# axiom_beta_interface_dummy_v0_11_1c4a0d4.net
KiCad netlist of a schematic drawn in EAGLE
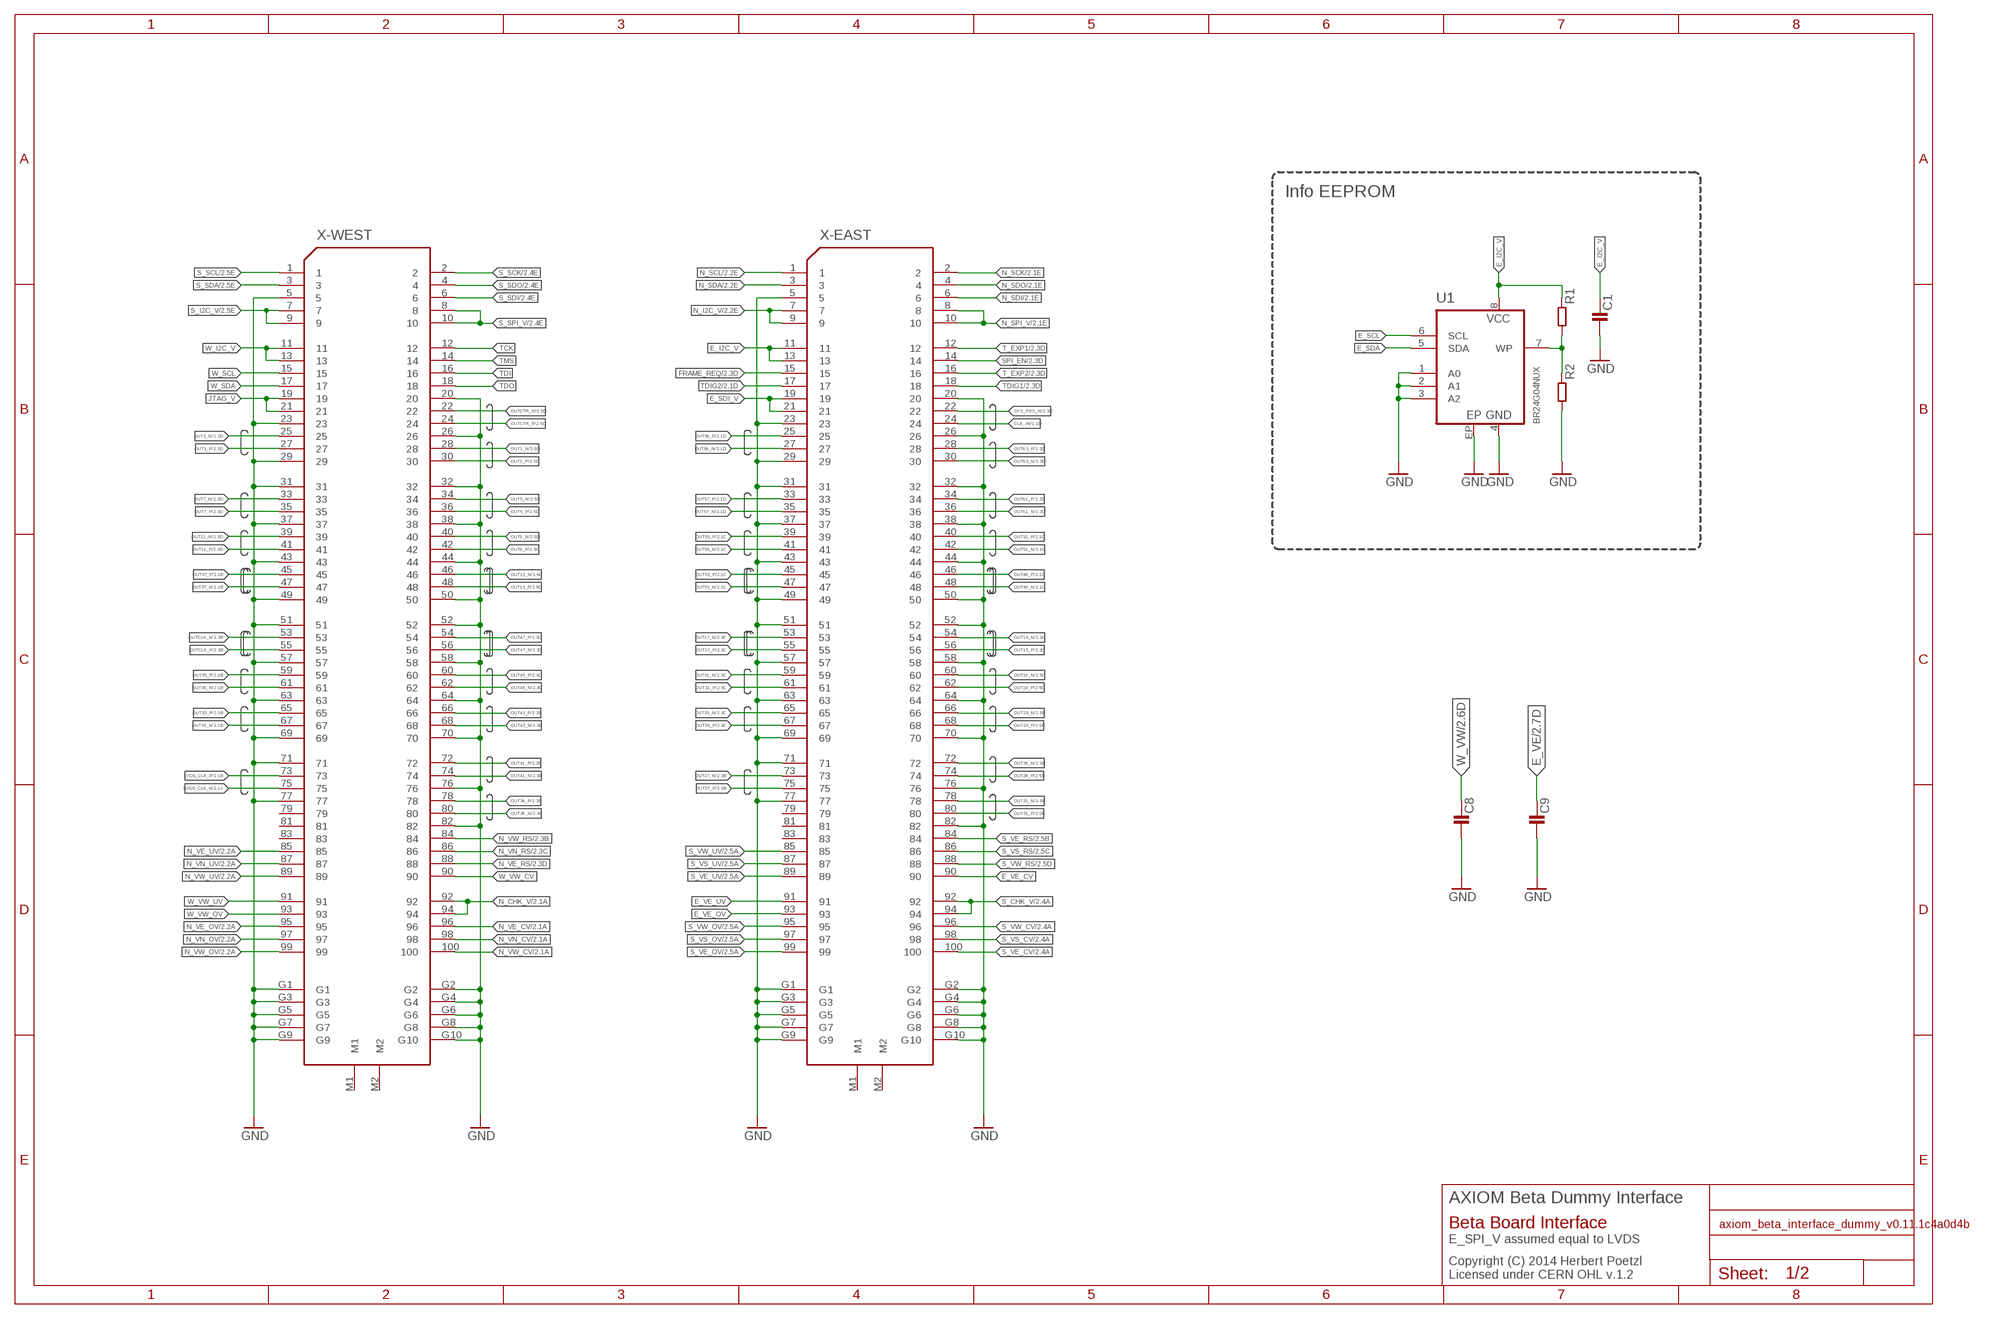
[diagram p0: schematic, sheet 1]
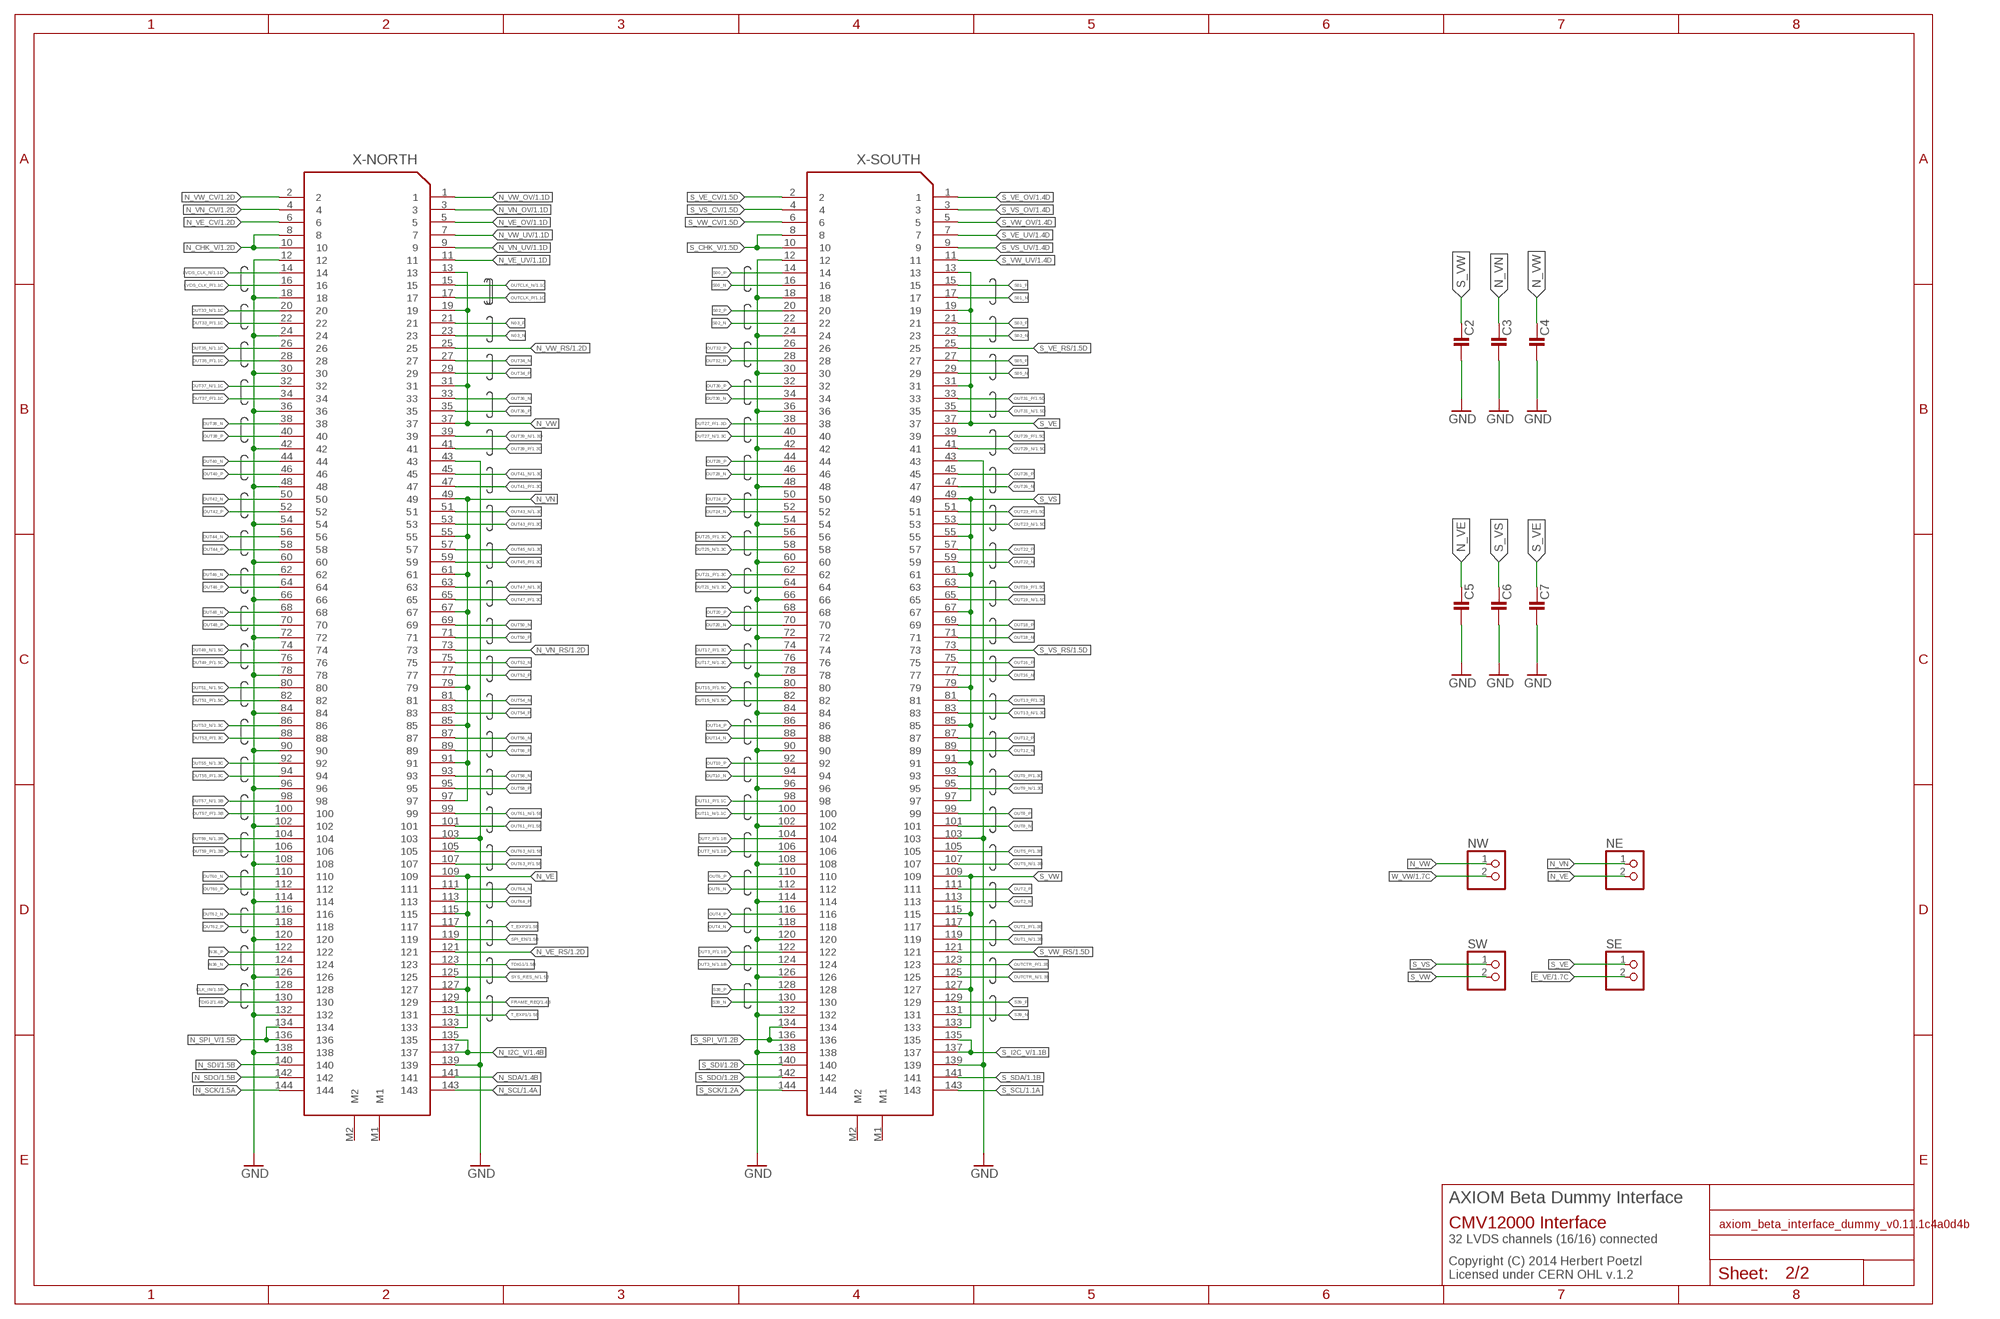
[diagram p1: schematic, sheet 2]

(export (version "E")
  (design (tool "Eeschema 10.0.6"))
  (components
    (comp (ref "C2")
      (value "C0805-B")
      (footprint "eagle-import:0805-B")
      (libsource (lib "eagle-import") (part "C0805-B"))
    )
    (comp (ref "C3")
      (value "C0805-B")
      (footprint "eagle-import:0805-B")
      (libsource (lib "eagle-import") (part "C0805-B"))
    )
    (comp (ref "C4")
      (value "C0805-B")
      (footprint "eagle-import:0805-B")
      (libsource (lib "eagle-import") (part "C0805-B"))
    )
    (comp (ref "C5")
      (value "C0805-B")
      (footprint "eagle-import:0805-B")
      (libsource (lib "eagle-import") (part "C0805-B"))
    )
    (comp (ref "C6")
      (value "C0805-B")
      (footprint "eagle-import:0805-B")
      (libsource (lib "eagle-import") (part "C0805-B"))
    )
    (comp (ref "C7")
      (value "C0805-B")
      (footprint "eagle-import:0805-B")
      (libsource (lib "eagle-import") (part "C0805-B"))
    )
    (comp (ref "NE")
      (value "PINHD-1X02_2.54")
      (footprint "eagle-import:1X02")
      (libsource (lib "eagle-import") (part "PINHD-1X02_2.54"))
    )
    (comp (ref "NW")
      (value "PINHD-1X02_2.54")
      (footprint "eagle-import:1X02")
      (libsource (lib "eagle-import") (part "PINHD-1X02_2.54"))
    )
    (comp (ref "SE")
      (value "PINHD-1X02_2.54")
      (footprint "eagle-import:1X02")
      (libsource (lib "eagle-import") (part "PINHD-1X02_2.54"))
    )
    (comp (ref "SW")
      (value "PINHD-1X02_2.54")
      (footprint "eagle-import:1X02")
      (libsource (lib "eagle-import") (part "PINHD-1X02_2.54"))
    )
    (comp (ref "X-NORTH")
      (value "FX10-144S")
      (footprint "eagle-import:FX10A-144S")
      (libsource (lib "eagle-import") (part "FX10-144S"))
    )
    (comp (ref "X-SOUTH")
      (value "FX10-144S")
      (footprint "eagle-import:FX10A-144S")
      (libsource (lib "eagle-import") (part "FX10-144S"))
    )
    (comp (ref "C1")
      (value "C0402-B")
      (footprint "eagle-import:0402-B")
      (libsource (lib "eagle-import") (part "C0402-B"))
    )
    (comp (ref "C8")
      (value "C0805-B")
      (footprint "eagle-import:0805-B")
      (libsource (lib "eagle-import") (part "C0805-B"))
    )
    (comp (ref "C9")
      (value "C0805-B")
      (footprint "eagle-import:0805-B")
      (libsource (lib "eagle-import") (part "C0805-B"))
    )
    (comp (ref "R1")
      (value "R0402-B")
      (footprint "eagle-import:0402-B")
      (libsource (lib "eagle-import") (part "R0402-B"))
    )
    (comp (ref "R2")
      (value "R0402-B")
      (footprint "eagle-import:0402-B")
      (libsource (lib "eagle-import") (part "R0402-B"))
    )
    (comp (ref "U1")
      (value "BR24G04NUX")
      (footprint "eagle-import:DFN200X300X100-9N")
      (libsource (lib "eagle-import") (part "BR24G04NUX"))
    )
    (comp (ref "X-EAST")
      (value "FX10-100/10P")
      (footprint "eagle-import:FX10A-100P_10")
      (libsource (lib "eagle-import") (part "FX10-100/10P"))
    )
    (comp (ref "X-WEST")
      (value "FX10-100/10P")
      (footprint "eagle-import:FX10A-100P_10")
      (libsource (lib "eagle-import") (part "FX10-100/10P"))
    )
  )
  (nets
    (net (code "1") (name "CLK_IN") (class "Default")
      (node (ref "X-EAST") (pin "24") (pinfunction "24_24") (pintype "bidirectional"))
      (node (ref "X-NORTH") (pin "128") (pinfunction "128_128") (pintype "bidirectional"))
    )
    (net (code "2") (name "E_I2C_V") (class "Default")
      (node (ref "C1") (pin "1") (pinfunction "1_1") (pintype "passive"))
      (node (ref "R1") (pin "1") (pinfunction "1_1") (pintype "passive"))
      (node (ref "U1") (pin "8") (pinfunction "VCC_8") (pintype "power_in"))
      (node (ref "X-EAST") (pin "11") (pinfunction "11_11") (pintype "bidirectional"))
      (node (ref "X-EAST") (pin "13") (pinfunction "13_13") (pintype "bidirectional"))
    )
    (net (code "3") (name "E_SCL") (class "Default")
      (node (ref "U1") (pin "6") (pinfunction "SCL_6") (pintype "input"))
    )
    (net (code "4") (name "E_SDA") (class "Default")
      (node (ref "U1") (pin "5") (pinfunction "SDA_5") (pintype "bidirectional"))
    )
    (net (code "5") (name "E_SDI_V") (class "Default")
      (node (ref "X-EAST") (pin "19") (pinfunction "19_19") (pintype "bidirectional"))
      (node (ref "X-EAST") (pin "21") (pinfunction "21_21") (pintype "bidirectional"))
    )
    (net (code "6") (name "E_VE") (class "Default")
      (node (ref "C9") (pin "1") (pinfunction "1_1") (pintype "passive"))
      (node (ref "SE") (pin "2") (pinfunction "2_2") (pintype "passive"))
    )
    (net (code "7") (name "E_VE_CV") (class "Default")
      (node (ref "X-EAST") (pin "90") (pinfunction "90_90") (pintype "bidirectional"))
    )
    (net (code "8") (name "E_VE_OV") (class "Default")
      (node (ref "X-EAST") (pin "93") (pinfunction "93_93") (pintype "bidirectional"))
    )
    (net (code "9") (name "E_VE_UV") (class "Default")
      (node (ref "X-EAST") (pin "91") (pinfunction "91_91") (pintype "bidirectional"))
    )
    (net (code "10") (name "FRAME_REQ") (class "Default")
      (node (ref "X-EAST") (pin "15") (pinfunction "15_15") (pintype "bidirectional"))
      (node (ref "X-NORTH") (pin "129") (pinfunction "129_129") (pintype "bidirectional"))
    )
    (net (code "11") (name "GND") (class "Default")
      (node (ref "C1") (pin "2") (pinfunction "2_2") (pintype "passive"))
      (node (ref "C2") (pin "2") (pinfunction "2_2") (pintype "passive"))
      (node (ref "C3") (pin "2") (pinfunction "2_2") (pintype "passive"))
      (node (ref "C4") (pin "2") (pinfunction "2_2") (pintype "passive"))
      (node (ref "C5") (pin "2") (pinfunction "2_2") (pintype "passive"))
      (node (ref "C6") (pin "2") (pinfunction "2_2") (pintype "passive"))
      (node (ref "C7") (pin "2") (pinfunction "2_2") (pintype "passive"))
      (node (ref "C8") (pin "2") (pinfunction "2_2") (pintype "passive"))
      (node (ref "C9") (pin "2") (pinfunction "2_2") (pintype "passive"))
      (node (ref "R2") (pin "2") (pinfunction "2_2") (pintype "passive"))
      (node (ref "U1") (pin "1") (pinfunction "A0_1") (pintype "input"))
      (node (ref "U1") (pin "2") (pinfunction "A1_2") (pintype "input"))
      (node (ref "U1") (pin "3") (pinfunction "A2_3") (pintype "input"))
      (node (ref "U1") (pin "4") (pinfunction "GND_4") (pintype "passive"))
      (node (ref "U1") (pin "EP") (pinfunction "EP_EP") (pintype "passive"))
      (node (ref "X-EAST") (pin "20") (pinfunction "20_20") (pintype "bidirectional"))
      (node (ref "X-EAST") (pin "23") (pinfunction "23_23") (pintype "bidirectional"))
      (node (ref "X-EAST") (pin "26") (pinfunction "26_26") (pintype "bidirectional"))
      (node (ref "X-EAST") (pin "29") (pinfunction "29_29") (pintype "bidirectional"))
      (node (ref "X-EAST") (pin "31") (pinfunction "31_31") (pintype "bidirectional"))
      (node (ref "X-EAST") (pin "32") (pinfunction "32_32") (pintype "bidirectional"))
      (node (ref "X-EAST") (pin "37") (pinfunction "37_37") (pintype "bidirectional"))
      (node (ref "X-EAST") (pin "38") (pinfunction "38_38") (pintype "bidirectional"))
      (node (ref "X-EAST") (pin "43") (pinfunction "43_43") (pintype "bidirectional"))
      (node (ref "X-EAST") (pin "44") (pinfunction "44_44") (pintype "bidirectional"))
      (node (ref "X-EAST") (pin "49") (pinfunction "49_49") (pintype "bidirectional"))
      (node (ref "X-EAST") (pin "5") (pinfunction "5_5") (pintype "bidirectional"))
      (node (ref "X-EAST") (pin "50") (pinfunction "50_50") (pintype "bidirectional"))
      (node (ref "X-EAST") (pin "51") (pinfunction "51_51") (pintype "bidirectional"))
      (node (ref "X-EAST") (pin "52") (pinfunction "52_52") (pintype "bidirectional"))
      (node (ref "X-EAST") (pin "57") (pinfunction "57_57") (pintype "bidirectional"))
      (node (ref "X-EAST") (pin "58") (pinfunction "58_58") (pintype "bidirectional"))
      (node (ref "X-EAST") (pin "63") (pinfunction "63_63") (pintype "bidirectional"))
      (node (ref "X-EAST") (pin "64") (pinfunction "64_64") (pintype "bidirectional"))
      (node (ref "X-EAST") (pin "69") (pinfunction "69_69") (pintype "bidirectional"))
      (node (ref "X-EAST") (pin "70") (pinfunction "70_70") (pintype "bidirectional"))
      (node (ref "X-EAST") (pin "71") (pinfunction "71_71") (pintype "bidirectional"))
      (node (ref "X-EAST") (pin "76") (pinfunction "76_76") (pintype "bidirectional"))
      (node (ref "X-EAST") (pin "77") (pinfunction "77_77") (pintype "bidirectional"))
      (node (ref "X-EAST") (pin "82") (pinfunction "82_82") (pintype "bidirectional"))
      (node (ref "X-EAST") (pin "G1") (pinfunction "G1_G1") (pintype "bidirectional"))
      (node (ref "X-EAST") (pin "G10") (pinfunction "G10_G10") (pintype "bidirectional"))
      (node (ref "X-EAST") (pin "G2") (pinfunction "G2_G2") (pintype "bidirectional"))
      (node (ref "X-EAST") (pin "G3") (pinfunction "G3_G3") (pintype "bidirectional"))
      (node (ref "X-EAST") (pin "G4") (pinfunction "G4_G4") (pintype "bidirectional"))
      (node (ref "X-EAST") (pin "G5") (pinfunction "G5_G5") (pintype "bidirectional"))
      (node (ref "X-EAST") (pin "G6") (pinfunction "G6_G6") (pintype "bidirectional"))
      (node (ref "X-EAST") (pin "G7") (pinfunction "G7_G7") (pintype "bidirectional"))
      (node (ref "X-EAST") (pin "G8") (pinfunction "G8_G8") (pintype "bidirectional"))
      (node (ref "X-EAST") (pin "G9") (pinfunction "G9_G9") (pintype "bidirectional"))
      (node (ref "X-NORTH") (pin "102") (pinfunction "102_102") (pintype "bidirectional"))
      (node (ref "X-NORTH") (pin "103") (pinfunction "103_103") (pintype "bidirectional"))
      (node (ref "X-NORTH") (pin "108") (pinfunction "108_108") (pintype "bidirectional"))
      (node (ref "X-NORTH") (pin "114") (pinfunction "114_114") (pintype "bidirectional"))
      (node (ref "X-NORTH") (pin "12") (pinfunction "12_12") (pintype "bidirectional"))
      (node (ref "X-NORTH") (pin "120") (pinfunction "120_120") (pintype "bidirectional"))
      (node (ref "X-NORTH") (pin "126") (pinfunction "126_126") (pintype "bidirectional"))
      (node (ref "X-NORTH") (pin "132") (pinfunction "132_132") (pintype "bidirectional"))
      (node (ref "X-NORTH") (pin "138") (pinfunction "138_138") (pintype "bidirectional"))
      (node (ref "X-NORTH") (pin "139") (pinfunction "139_139") (pintype "bidirectional"))
      (node (ref "X-NORTH") (pin "18") (pinfunction "18_18") (pintype "bidirectional"))
      (node (ref "X-NORTH") (pin "24") (pinfunction "24_24") (pintype "bidirectional"))
      (node (ref "X-NORTH") (pin "30") (pinfunction "30_30") (pintype "bidirectional"))
      (node (ref "X-NORTH") (pin "36") (pinfunction "36_36") (pintype "bidirectional"))
      (node (ref "X-NORTH") (pin "42") (pinfunction "42_42") (pintype "bidirectional"))
      (node (ref "X-NORTH") (pin "43") (pinfunction "43_43") (pintype "bidirectional"))
      (node (ref "X-NORTH") (pin "48") (pinfunction "48_48") (pintype "bidirectional"))
      (node (ref "X-NORTH") (pin "54") (pinfunction "54_54") (pintype "bidirectional"))
      (node (ref "X-NORTH") (pin "60") (pinfunction "60_60") (pintype "bidirectional"))
      (node (ref "X-NORTH") (pin "66") (pinfunction "66_66") (pintype "bidirectional"))
      (node (ref "X-NORTH") (pin "72") (pinfunction "72_72") (pintype "bidirectional"))
      (node (ref "X-NORTH") (pin "78") (pinfunction "78_78") (pintype "bidirectional"))
      (node (ref "X-NORTH") (pin "84") (pinfunction "84_84") (pintype "bidirectional"))
      (node (ref "X-NORTH") (pin "90") (pinfunction "90_90") (pintype "bidirectional"))
      (node (ref "X-NORTH") (pin "96") (pinfunction "96_96") (pintype "bidirectional"))
      (node (ref "X-SOUTH") (pin "102") (pinfunction "102_102") (pintype "bidirectional"))
      (node (ref "X-SOUTH") (pin "103") (pinfunction "103_103") (pintype "bidirectional"))
      (node (ref "X-SOUTH") (pin "108") (pinfunction "108_108") (pintype "bidirectional"))
      (node (ref "X-SOUTH") (pin "114") (pinfunction "114_114") (pintype "bidirectional"))
      (node (ref "X-SOUTH") (pin "12") (pinfunction "12_12") (pintype "bidirectional"))
      (node (ref "X-SOUTH") (pin "120") (pinfunction "120_120") (pintype "bidirectional"))
      (node (ref "X-SOUTH") (pin "126") (pinfunction "126_126") (pintype "bidirectional"))
      (node (ref "X-SOUTH") (pin "132") (pinfunction "132_132") (pintype "bidirectional"))
      (node (ref "X-SOUTH") (pin "138") (pinfunction "138_138") (pintype "bidirectional"))
      (node (ref "X-SOUTH") (pin "139") (pinfunction "139_139") (pintype "bidirectional"))
      (node (ref "X-SOUTH") (pin "18") (pinfunction "18_18") (pintype "bidirectional"))
      (node (ref "X-SOUTH") (pin "24") (pinfunction "24_24") (pintype "bidirectional"))
      (node (ref "X-SOUTH") (pin "30") (pinfunction "30_30") (pintype "bidirectional"))
      (node (ref "X-SOUTH") (pin "36") (pinfunction "36_36") (pintype "bidirectional"))
      (node (ref "X-SOUTH") (pin "42") (pinfunction "42_42") (pintype "bidirectional"))
      (node (ref "X-SOUTH") (pin "43") (pinfunction "43_43") (pintype "bidirectional"))
      (node (ref "X-SOUTH") (pin "48") (pinfunction "48_48") (pintype "bidirectional"))
      (node (ref "X-SOUTH") (pin "54") (pinfunction "54_54") (pintype "bidirectional"))
      (node (ref "X-SOUTH") (pin "60") (pinfunction "60_60") (pintype "bidirectional"))
      (node (ref "X-SOUTH") (pin "66") (pinfunction "66_66") (pintype "bidirectional"))
      (node (ref "X-SOUTH") (pin "72") (pinfunction "72_72") (pintype "bidirectional"))
      (node (ref "X-SOUTH") (pin "78") (pinfunction "78_78") (pintype "bidirectional"))
      (node (ref "X-SOUTH") (pin "84") (pinfunction "84_84") (pintype "bidirectional"))
      (node (ref "X-SOUTH") (pin "90") (pinfunction "90_90") (pintype "bidirectional"))
      (node (ref "X-SOUTH") (pin "96") (pinfunction "96_96") (pintype "bidirectional"))
      (node (ref "X-WEST") (pin "20") (pinfunction "20_20") (pintype "bidirectional"))
      (node (ref "X-WEST") (pin "23") (pinfunction "23_23") (pintype "bidirectional"))
      (node (ref "X-WEST") (pin "26") (pinfunction "26_26") (pintype "bidirectional"))
      (node (ref "X-WEST") (pin "29") (pinfunction "29_29") (pintype "bidirectional"))
      (node (ref "X-WEST") (pin "31") (pinfunction "31_31") (pintype "bidirectional"))
      (node (ref "X-WEST") (pin "32") (pinfunction "32_32") (pintype "bidirectional"))
      (node (ref "X-WEST") (pin "37") (pinfunction "37_37") (pintype "bidirectional"))
      (node (ref "X-WEST") (pin "38") (pinfunction "38_38") (pintype "bidirectional"))
      (node (ref "X-WEST") (pin "43") (pinfunction "43_43") (pintype "bidirectional"))
      (node (ref "X-WEST") (pin "44") (pinfunction "44_44") (pintype "bidirectional"))
      (node (ref "X-WEST") (pin "49") (pinfunction "49_49") (pintype "bidirectional"))
      (node (ref "X-WEST") (pin "5") (pinfunction "5_5") (pintype "bidirectional"))
      (node (ref "X-WEST") (pin "50") (pinfunction "50_50") (pintype "bidirectional"))
      (node (ref "X-WEST") (pin "51") (pinfunction "51_51") (pintype "bidirectional"))
      (node (ref "X-WEST") (pin "52") (pinfunction "52_52") (pintype "bidirectional"))
      (node (ref "X-WEST") (pin "57") (pinfunction "57_57") (pintype "bidirectional"))
      (node (ref "X-WEST") (pin "58") (pinfunction "58_58") (pintype "bidirectional"))
      (node (ref "X-WEST") (pin "63") (pinfunction "63_63") (pintype "bidirectional"))
      (node (ref "X-WEST") (pin "64") (pinfunction "64_64") (pintype "bidirectional"))
      (node (ref "X-WEST") (pin "69") (pinfunction "69_69") (pintype "bidirectional"))
      (node (ref "X-WEST") (pin "70") (pinfunction "70_70") (pintype "bidirectional"))
      (node (ref "X-WEST") (pin "71") (pinfunction "71_71") (pintype "bidirectional"))
      (node (ref "X-WEST") (pin "76") (pinfunction "76_76") (pintype "bidirectional"))
      (node (ref "X-WEST") (pin "77") (pinfunction "77_77") (pintype "bidirectional"))
      (node (ref "X-WEST") (pin "82") (pinfunction "82_82") (pintype "bidirectional"))
      (node (ref "X-WEST") (pin "G1") (pinfunction "G1_G1") (pintype "bidirectional"))
      (node (ref "X-WEST") (pin "G10") (pinfunction "G10_G10") (pintype "bidirectional"))
      (node (ref "X-WEST") (pin "G2") (pinfunction "G2_G2") (pintype "bidirectional"))
      (node (ref "X-WEST") (pin "G3") (pinfunction "G3_G3") (pintype "bidirectional"))
      (node (ref "X-WEST") (pin "G4") (pinfunction "G4_G4") (pintype "bidirectional"))
      (node (ref "X-WEST") (pin "G5") (pinfunction "G5_G5") (pintype "bidirectional"))
      (node (ref "X-WEST") (pin "G6") (pinfunction "G6_G6") (pintype "bidirectional"))
      (node (ref "X-WEST") (pin "G7") (pinfunction "G7_G7") (pintype "bidirectional"))
      (node (ref "X-WEST") (pin "G8") (pinfunction "G8_G8") (pintype "bidirectional"))
      (node (ref "X-WEST") (pin "G9") (pinfunction "G9_G9") (pintype "bidirectional"))
    )
    (net (code "12") (name "JTAG_V") (class "Default")
      (node (ref "X-WEST") (pin "19") (pinfunction "19_19") (pintype "bidirectional"))
      (node (ref "X-WEST") (pin "21") (pinfunction "21_21") (pintype "bidirectional"))
    )
    (net (code "13") (name "LVDS_CLK_N") (class "Default")
      (node (ref "X-NORTH") (pin "14") (pinfunction "14_14") (pintype "bidirectional"))
      (node (ref "X-WEST") (pin "75") (pinfunction "75_75") (pintype "bidirectional"))
    )
    (net (code "14") (name "LVDS_CLK_P") (class "Default")
      (node (ref "X-NORTH") (pin "16") (pinfunction "16_16") (pintype "bidirectional"))
      (node (ref "X-WEST") (pin "73") (pinfunction "73_73") (pintype "bidirectional"))
    )
    (net (code "15") (name "N03_N") (class "Default")
      (node (ref "X-NORTH") (pin "23") (pinfunction "23_23") (pintype "bidirectional"))
    )
    (net (code "16") (name "N03_P") (class "Default")
      (node (ref "X-NORTH") (pin "21") (pinfunction "21_21") (pintype "bidirectional"))
    )
    (net (code "17") (name "N36_N") (class "Default")
      (node (ref "X-NORTH") (pin "124") (pinfunction "124_124") (pintype "bidirectional"))
    )
    (net (code "18") (name "N36_P") (class "Default")
      (node (ref "X-NORTH") (pin "122") (pinfunction "122_122") (pintype "bidirectional"))
    )
    (net (code "19") (name "N_CHK_V") (class "Default")
      (node (ref "X-NORTH") (pin "10") (pinfunction "10_10") (pintype "bidirectional"))
      (node (ref "X-NORTH") (pin "8") (pinfunction "8_8") (pintype "bidirectional"))
      (node (ref "X-WEST") (pin "92") (pinfunction "92_92") (pintype "bidirectional"))
      (node (ref "X-WEST") (pin "94") (pinfunction "94_94") (pintype "bidirectional"))
    )
    (net (code "20") (name "N_I2C_V") (class "Default")
      (node (ref "X-EAST") (pin "7") (pinfunction "7_7") (pintype "bidirectional"))
      (node (ref "X-EAST") (pin "9") (pinfunction "9_9") (pintype "bidirectional"))
      (node (ref "X-NORTH") (pin "135") (pinfunction "135_135") (pintype "bidirectional"))
      (node (ref "X-NORTH") (pin "137") (pinfunction "137_137") (pintype "bidirectional"))
    )
    (net (code "21") (name "N_SCK") (class "Default")
      (node (ref "X-EAST") (pin "2") (pinfunction "2_2") (pintype "bidirectional"))
      (node (ref "X-NORTH") (pin "144") (pinfunction "144_144") (pintype "bidirectional"))
    )
    (net (code "22") (name "N_SCL") (class "Default")
      (node (ref "X-EAST") (pin "1") (pinfunction "1_1") (pintype "bidirectional"))
      (node (ref "X-NORTH") (pin "143") (pinfunction "143_143") (pintype "bidirectional"))
    )
    (net (code "23") (name "N_SDA") (class "Default")
      (node (ref "X-EAST") (pin "3") (pinfunction "3_3") (pintype "bidirectional"))
      (node (ref "X-NORTH") (pin "141") (pinfunction "141_141") (pintype "bidirectional"))
    )
    (net (code "24") (name "N_SDI") (class "Default")
      (node (ref "X-EAST") (pin "6") (pinfunction "6_6") (pintype "bidirectional"))
      (node (ref "X-NORTH") (pin "140") (pinfunction "140_140") (pintype "bidirectional"))
    )
    (net (code "25") (name "N_SDO") (class "Default")
      (node (ref "X-EAST") (pin "4") (pinfunction "4_4") (pintype "bidirectional"))
      (node (ref "X-NORTH") (pin "142") (pinfunction "142_142") (pintype "bidirectional"))
    )
    (net (code "26") (name "N_SPI_V") (class "Default")
      (node (ref "X-EAST") (pin "10") (pinfunction "10_10") (pintype "bidirectional"))
      (node (ref "X-EAST") (pin "8") (pinfunction "8_8") (pintype "bidirectional"))
      (node (ref "X-NORTH") (pin "134") (pinfunction "134_134") (pintype "bidirectional"))
      (node (ref "X-NORTH") (pin "136") (pinfunction "136_136") (pintype "bidirectional"))
    )
    (net (code "27") (name "N_VE") (class "Default")
      (node (ref "C5") (pin "1") (pinfunction "1_1") (pintype "passive"))
      (node (ref "NE") (pin "2") (pinfunction "2_2") (pintype "passive"))
      (node (ref "X-NORTH") (pin "109") (pinfunction "109_109") (pintype "bidirectional"))
      (node (ref "X-NORTH") (pin "115") (pinfunction "115_115") (pintype "bidirectional"))
      (node (ref "X-NORTH") (pin "127") (pinfunction "127_127") (pintype "bidirectional"))
      (node (ref "X-NORTH") (pin "133") (pinfunction "133_133") (pintype "bidirectional"))
    )
    (net (code "28") (name "N_VE_CV") (class "Default")
      (node (ref "X-NORTH") (pin "6") (pinfunction "6_6") (pintype "bidirectional"))
      (node (ref "X-WEST") (pin "96") (pinfunction "96_96") (pintype "bidirectional"))
    )
    (net (code "29") (name "N_VE_OV") (class "Default")
      (node (ref "X-NORTH") (pin "5") (pinfunction "5_5") (pintype "bidirectional"))
      (node (ref "X-WEST") (pin "95") (pinfunction "95_95") (pintype "bidirectional"))
    )
    (net (code "30") (name "N_VE_RS") (class "Default")
      (node (ref "X-NORTH") (pin "121") (pinfunction "121_121") (pintype "bidirectional"))
      (node (ref "X-WEST") (pin "88") (pinfunction "88_88") (pintype "bidirectional"))
    )
    (net (code "31") (name "N_VE_UV") (class "Default")
      (node (ref "X-NORTH") (pin "11") (pinfunction "11_11") (pintype "bidirectional"))
      (node (ref "X-WEST") (pin "85") (pinfunction "85_85") (pintype "bidirectional"))
    )
    (net (code "32") (name "N_VN") (class "Default")
      (node (ref "C3") (pin "1") (pinfunction "1_1") (pintype "passive"))
      (node (ref "NE") (pin "1") (pinfunction "1_1") (pintype "passive"))
      (node (ref "X-NORTH") (pin "49") (pinfunction "49_49") (pintype "bidirectional"))
      (node (ref "X-NORTH") (pin "55") (pinfunction "55_55") (pintype "bidirectional"))
      (node (ref "X-NORTH") (pin "61") (pinfunction "61_61") (pintype "bidirectional"))
      (node (ref "X-NORTH") (pin "67") (pinfunction "67_67") (pintype "bidirectional"))
      (node (ref "X-NORTH") (pin "79") (pinfunction "79_79") (pintype "bidirectional"))
      (node (ref "X-NORTH") (pin "85") (pinfunction "85_85") (pintype "bidirectional"))
      (node (ref "X-NORTH") (pin "91") (pinfunction "91_91") (pintype "bidirectional"))
      (node (ref "X-NORTH") (pin "97") (pinfunction "97_97") (pintype "bidirectional"))
    )
    (net (code "33") (name "N_VN_CV") (class "Default")
      (node (ref "X-NORTH") (pin "4") (pinfunction "4_4") (pintype "bidirectional"))
      (node (ref "X-WEST") (pin "98") (pinfunction "98_98") (pintype "bidirectional"))
    )
    (net (code "34") (name "N_VN_OV") (class "Default")
      (node (ref "X-NORTH") (pin "3") (pinfunction "3_3") (pintype "bidirectional"))
      (node (ref "X-WEST") (pin "97") (pinfunction "97_97") (pintype "bidirectional"))
    )
    (net (code "35") (name "N_VN_RS") (class "Default")
      (node (ref "X-NORTH") (pin "73") (pinfunction "73_73") (pintype "bidirectional"))
      (node (ref "X-WEST") (pin "86") (pinfunction "86_86") (pintype "bidirectional"))
    )
    (net (code "36") (name "N_VN_UV") (class "Default")
      (node (ref "X-NORTH") (pin "9") (pinfunction "9_9") (pintype "bidirectional"))
      (node (ref "X-WEST") (pin "87") (pinfunction "87_87") (pintype "bidirectional"))
    )
    (net (code "37") (name "N_VW") (class "Default")
      (node (ref "C4") (pin "1") (pinfunction "1_1") (pintype "passive"))
      (node (ref "NW") (pin "1") (pinfunction "1_1") (pintype "passive"))
      (node (ref "X-NORTH") (pin "13") (pinfunction "13_13") (pintype "bidirectional"))
      (node (ref "X-NORTH") (pin "19") (pinfunction "19_19") (pintype "bidirectional"))
      (node (ref "X-NORTH") (pin "31") (pinfunction "31_31") (pintype "bidirectional"))
      (node (ref "X-NORTH") (pin "37") (pinfunction "37_37") (pintype "bidirectional"))
    )
    (net (code "38") (name "N_VW_CV") (class "Default")
      (node (ref "X-NORTH") (pin "2") (pinfunction "2_2") (pintype "bidirectional"))
      (node (ref "X-WEST") (pin "100") (pinfunction "100_100") (pintype "bidirectional"))
    )
    (net (code "39") (name "N_VW_OV") (class "Default")
      (node (ref "X-NORTH") (pin "1") (pinfunction "1_1") (pintype "bidirectional"))
      (node (ref "X-WEST") (pin "99") (pinfunction "99_99") (pintype "bidirectional"))
    )
    (net (code "40") (name "N_VW_RS") (class "Default")
      (node (ref "X-NORTH") (pin "25") (pinfunction "25_25") (pintype "bidirectional"))
      (node (ref "X-WEST") (pin "84") (pinfunction "84_84") (pintype "bidirectional"))
    )
    (net (code "41") (name "N_VW_UV") (class "Default")
      (node (ref "X-NORTH") (pin "7") (pinfunction "7_7") (pintype "bidirectional"))
      (node (ref "X-WEST") (pin "89") (pinfunction "89_89") (pintype "bidirectional"))
    )
    (net (code "42") (name "Net-(U1-WP)") (class "Default")
      (node (ref "R1") (pin "2") (pinfunction "2_2") (pintype "passive"))
      (node (ref "R2") (pin "1") (pinfunction "1_1") (pintype "passive"))
      (node (ref "U1") (pin "7") (pinfunction "WP_7") (pintype "input"))
    )
    (net (code "43") (name "OUT1_N") (class "Default")
      (node (ref "X-SOUTH") (pin "119") (pinfunction "119_119") (pintype "bidirectional"))
      (node (ref "X-WEST") (pin "28") (pinfunction "28_28") (pintype "bidirectional"))
    )
    (net (code "44") (name "OUT1_P") (class "Default")
      (node (ref "X-SOUTH") (pin "117") (pinfunction "117_117") (pintype "bidirectional"))
      (node (ref "X-WEST") (pin "30") (pinfunction "30_30") (pintype "bidirectional"))
    )
    (net (code "45") (name "OUT2_N") (class "Default")
      (node (ref "X-SOUTH") (pin "113") (pinfunction "113_113") (pintype "bidirectional"))
    )
    (net (code "46") (name "OUT2_P") (class "Default")
      (node (ref "X-SOUTH") (pin "111") (pinfunction "111_111") (pintype "bidirectional"))
    )
    (net (code "47") (name "OUT3_N") (class "Default")
      (node (ref "X-SOUTH") (pin "124") (pinfunction "124_124") (pintype "bidirectional"))
      (node (ref "X-WEST") (pin "25") (pinfunction "25_25") (pintype "bidirectional"))
    )
    (net (code "48") (name "OUT3_P") (class "Default")
      (node (ref "X-SOUTH") (pin "122") (pinfunction "122_122") (pintype "bidirectional"))
      (node (ref "X-WEST") (pin "27") (pinfunction "27_27") (pintype "bidirectional"))
    )
    (net (code "49") (name "OUT4_N") (class "Default")
      (node (ref "X-SOUTH") (pin "118") (pinfunction "118_118") (pintype "bidirectional"))
    )
    (net (code "50") (name "OUT4_P") (class "Default")
      (node (ref "X-SOUTH") (pin "116") (pinfunction "116_116") (pintype "bidirectional"))
    )
    (net (code "51") (name "OUT5_N") (class "Default")
      (node (ref "X-SOUTH") (pin "107") (pinfunction "107_107") (pintype "bidirectional"))
      (node (ref "X-WEST") (pin "34") (pinfunction "34_34") (pintype "bidirectional"))
    )
    (net (code "52") (name "OUT5_P") (class "Default")
      (node (ref "X-SOUTH") (pin "105") (pinfunction "105_105") (pintype "bidirectional"))
      (node (ref "X-WEST") (pin "36") (pinfunction "36_36") (pintype "bidirectional"))
    )
    (net (code "53") (name "OUT6_N") (class "Default")
      (node (ref "X-SOUTH") (pin "112") (pinfunction "112_112") (pintype "bidirectional"))
    )
    (net (code "54") (name "OUT6_P") (class "Default")
      (node (ref "X-SOUTH") (pin "110") (pinfunction "110_110") (pintype "bidirectional"))
    )
    (net (code "55") (name "OUT7_N") (class "Default")
      (node (ref "X-SOUTH") (pin "106") (pinfunction "106_106") (pintype "bidirectional"))
      (node (ref "X-WEST") (pin "33") (pinfunction "33_33") (pintype "bidirectional"))
    )
    (net (code "56") (name "OUT7_P") (class "Default")
      (node (ref "X-SOUTH") (pin "104") (pinfunction "104_104") (pintype "bidirectional"))
      (node (ref "X-WEST") (pin "35") (pinfunction "35_35") (pintype "bidirectional"))
    )
    (net (code "57") (name "OUT8_N") (class "Default")
      (node (ref "X-SOUTH") (pin "101") (pinfunction "101_101") (pintype "bidirectional"))
    )
    (net (code "58") (name "OUT8_P") (class "Default")
      (node (ref "X-SOUTH") (pin "99") (pinfunction "99_99") (pintype "bidirectional"))
    )
    (net (code "59") (name "OUT9_N") (class "Default")
      (node (ref "X-SOUTH") (pin "95") (pinfunction "95_95") (pintype "bidirectional"))
      (node (ref "X-WEST") (pin "40") (pinfunction "40_40") (pintype "bidirectional"))
    )
    (net (code "60") (name "OUT9_P") (class "Default")
      (node (ref "X-SOUTH") (pin "93") (pinfunction "93_93") (pintype "bidirectional"))
      (node (ref "X-WEST") (pin "42") (pinfunction "42_42") (pintype "bidirectional"))
    )
    (net (code "61") (name "OUT10_N") (class "Default")
      (node (ref "X-SOUTH") (pin "94") (pinfunction "94_94") (pintype "bidirectional"))
    )
    (net (code "62") (name "OUT10_P") (class "Default")
      (node (ref "X-SOUTH") (pin "92") (pinfunction "92_92") (pintype "bidirectional"))
    )
    (net (code "63") (name "OUT11_N") (class "Default")
      (node (ref "X-SOUTH") (pin "100") (pinfunction "100_100") (pintype "bidirectional"))
      (node (ref "X-WEST") (pin "39") (pinfunction "39_39") (pintype "bidirectional"))
    )
    (net (code "64") (name "OUT11_P") (class "Default")
      (node (ref "X-SOUTH") (pin "98") (pinfunction "98_98") (pintype "bidirectional"))
      (node (ref "X-WEST") (pin "41") (pinfunction "41_41") (pintype "bidirectional"))
    )
    (net (code "65") (name "OUT12_N") (class "Default")
      (node (ref "X-SOUTH") (pin "89") (pinfunction "89_89") (pintype "bidirectional"))
    )
    (net (code "66") (name "OUT12_P") (class "Default")
      (node (ref "X-SOUTH") (pin "87") (pinfunction "87_87") (pintype "bidirectional"))
    )
    (net (code "67") (name "OUT13_N") (class "Default")
      (node (ref "X-SOUTH") (pin "83") (pinfunction "83_83") (pintype "bidirectional"))
      (node (ref "X-WEST") (pin "46") (pinfunction "46_46") (pintype "bidirectional"))
    )
    (net (code "68") (name "OUT13_P") (class "Default")
      (node (ref "X-SOUTH") (pin "81") (pinfunction "81_81") (pintype "bidirectional"))
      (node (ref "X-WEST") (pin "48") (pinfunction "48_48") (pintype "bidirectional"))
    )
    (net (code "69") (name "OUT14_N") (class "Default")
      (node (ref "X-SOUTH") (pin "88") (pinfunction "88_88") (pintype "bidirectional"))
    )
    (net (code "70") (name "OUT14_P") (class "Default")
      (node (ref "X-SOUTH") (pin "86") (pinfunction "86_86") (pintype "bidirectional"))
    )
    (net (code "71") (name "OUT15_N") (class "Default")
      (node (ref "X-EAST") (pin "54") (pinfunction "54_54") (pintype "bidirectional"))
      (node (ref "X-SOUTH") (pin "82") (pinfunction "82_82") (pintype "bidirectional"))
    )
    (net (code "72") (name "OUT15_P") (class "Default")
      (node (ref "X-EAST") (pin "56") (pinfunction "56_56") (pintype "bidirectional"))
      (node (ref "X-SOUTH") (pin "80") (pinfunction "80_80") (pintype "bidirectional"))
    )
    (net (code "73") (name "OUT16_N") (class "Default")
      (node (ref "X-SOUTH") (pin "77") (pinfunction "77_77") (pintype "bidirectional"))
    )
    (net (code "74") (name "OUT16_P") (class "Default")
      (node (ref "X-SOUTH") (pin "75") (pinfunction "75_75") (pintype "bidirectional"))
    )
    (net (code "75") (name "OUT17_N") (class "Default")
      (node (ref "X-EAST") (pin "53") (pinfunction "53_53") (pintype "bidirectional"))
      (node (ref "X-SOUTH") (pin "76") (pinfunction "76_76") (pintype "bidirectional"))
    )
    (net (code "76") (name "OUT17_P") (class "Default")
      (node (ref "X-EAST") (pin "55") (pinfunction "55_55") (pintype "bidirectional"))
      (node (ref "X-SOUTH") (pin "74") (pinfunction "74_74") (pintype "bidirectional"))
    )
    (net (code "77") (name "OUT18_N") (class "Default")
      (node (ref "X-SOUTH") (pin "71") (pinfunction "71_71") (pintype "bidirectional"))
    )
    (net (code "78") (name "OUT18_P") (class "Default")
      (node (ref "X-SOUTH") (pin "69") (pinfunction "69_69") (pintype "bidirectional"))
    )
    (net (code "79") (name "OUT19_N") (class "Default")
      (node (ref "X-EAST") (pin "60") (pinfunction "60_60") (pintype "bidirectional"))
      (node (ref "X-SOUTH") (pin "65") (pinfunction "65_65") (pintype "bidirectional"))
    )
    (net (code "80") (name "OUT19_P") (class "Default")
      (node (ref "X-EAST") (pin "62") (pinfunction "62_62") (pintype "bidirectional"))
      (node (ref "X-SOUTH") (pin "63") (pinfunction "63_63") (pintype "bidirectional"))
    )
    (net (code "81") (name "OUT20_N") (class "Default")
      (node (ref "X-SOUTH") (pin "70") (pinfunction "70_70") (pintype "bidirectional"))
    )
    (net (code "82") (name "OUT20_P") (class "Default")
      (node (ref "X-SOUTH") (pin "68") (pinfunction "68_68") (pintype "bidirectional"))
    )
    (net (code "83") (name "OUT21_N") (class "Default")
      (node (ref "X-EAST") (pin "59") (pinfunction "59_59") (pintype "bidirectional"))
      (node (ref "X-SOUTH") (pin "64") (pinfunction "64_64") (pintype "bidirectional"))
    )
    (net (code "84") (name "OUT21_P") (class "Default")
      (node (ref "X-EAST") (pin "61") (pinfunction "61_61") (pintype "bidirectional"))
      (node (ref "X-SOUTH") (pin "62") (pinfunction "62_62") (pintype "bidirectional"))
    )
    (net (code "85") (name "OUT22_N") (class "Default")
      (node (ref "X-SOUTH") (pin "59") (pinfunction "59_59") (pintype "bidirectional"))
    )
    (net (code "86") (name "OUT22_P") (class "Default")
      (node (ref "X-SOUTH") (pin "57") (pinfunction "57_57") (pintype "bidirectional"))
    )
    (net (code "87") (name "OUT23_N") (class "Default")
      (node (ref "X-EAST") (pin "66") (pinfunction "66_66") (pintype "bidirectional"))
      (node (ref "X-SOUTH") (pin "53") (pinfunction "53_53") (pintype "bidirectional"))
    )
    (net (code "88") (name "OUT23_P") (class "Default")
      (node (ref "X-EAST") (pin "68") (pinfunction "68_68") (pintype "bidirectional"))
      (node (ref "X-SOUTH") (pin "51") (pinfunction "51_51") (pintype "bidirectional"))
    )
    (net (code "89") (name "OUT24_N") (class "Default")
      (node (ref "X-SOUTH") (pin "52") (pinfunction "52_52") (pintype "bidirectional"))
    )
    (net (code "90") (name "OUT24_P") (class "Default")
      (node (ref "X-SOUTH") (pin "50") (pinfunction "50_50") (pintype "bidirectional"))
    )
    (net (code "91") (name "OUT25_N") (class "Default")
      (node (ref "X-EAST") (pin "65") (pinfunction "65_65") (pintype "bidirectional"))
      (node (ref "X-SOUTH") (pin "58") (pinfunction "58_58") (pintype "bidirectional"))
    )
    (net (code "92") (name "OUT25_P") (class "Default")
      (node (ref "X-EAST") (pin "67") (pinfunction "67_67") (pintype "bidirectional"))
      (node (ref "X-SOUTH") (pin "56") (pinfunction "56_56") (pintype "bidirectional"))
    )
    (net (code "93") (name "OUT26_N") (class "Default")
      (node (ref "X-SOUTH") (pin "47") (pinfunction "47_47") (pintype "bidirectional"))
    )
    (net (code "94") (name "OUT26_P") (class "Default")
      (node (ref "X-SOUTH") (pin "45") (pinfunction "45_45") (pintype "bidirectional"))
    )
    (net (code "95") (name "OUT27_N") (class "Default")
      (node (ref "X-EAST") (pin "73") (pinfunction "73_73") (pintype "bidirectional"))
      (node (ref "X-SOUTH") (pin "40") (pinfunction "40_40") (pintype "bidirectional"))
    )
    (net (code "96") (name "OUT27_P") (class "Default")
      (node (ref "X-EAST") (pin "75") (pinfunction "75_75") (pintype "bidirectional"))
      (node (ref "X-SOUTH") (pin "38") (pinfunction "38_38") (pintype "bidirectional"))
    )
    (net (code "97") (name "OUT28_N") (class "Default")
      (node (ref "X-SOUTH") (pin "46") (pinfunction "46_46") (pintype "bidirectional"))
    )
    (net (code "98") (name "OUT28_P") (class "Default")
      (node (ref "X-SOUTH") (pin "44") (pinfunction "44_44") (pintype "bidirectional"))
    )
    (net (code "99") (name "OUT29_N") (class "Default")
      (node (ref "X-EAST") (pin "72") (pinfunction "72_72") (pintype "bidirectional"))
      (node (ref "X-SOUTH") (pin "41") (pinfunction "41_41") (pintype "bidirectional"))
    )
    (net (code "100") (name "OUT29_P") (class "Default")
      (node (ref "X-EAST") (pin "74") (pinfunction "74_74") (pintype "bidirectional"))
      (node (ref "X-SOUTH") (pin "39") (pinfunction "39_39") (pintype "bidirectional"))
    )
    (net (code "101") (name "OUT30_N") (class "Default")
      (node (ref "X-SOUTH") (pin "34") (pinfunction "34_34") (pintype "bidirectional"))
    )
    (net (code "102") (name "OUT30_P") (class "Default")
      (node (ref "X-SOUTH") (pin "32") (pinfunction "32_32") (pintype "bidirectional"))
    )
    (net (code "103") (name "OUT31_N") (class "Default")
      (node (ref "X-EAST") (pin "78") (pinfunction "78_78") (pintype "bidirectional"))
      (node (ref "X-SOUTH") (pin "35") (pinfunction "35_35") (pintype "bidirectional"))
    )
    (net (code "104") (name "OUT31_P") (class "Default")
      (node (ref "X-EAST") (pin "80") (pinfunction "80_80") (pintype "bidirectional"))
      (node (ref "X-SOUTH") (pin "33") (pinfunction "33_33") (pintype "bidirectional"))
    )
    (net (code "105") (name "OUT32_N") (class "Default")
      (node (ref "X-SOUTH") (pin "28") (pinfunction "28_28") (pintype "bidirectional"))
    )
    (net (code "106") (name "OUT32_P") (class "Default")
      (node (ref "X-SOUTH") (pin "26") (pinfunction "26_26") (pintype "bidirectional"))
    )
    (net (code "107") (name "OUT33_N") (class "Default")
      (node (ref "X-NORTH") (pin "20") (pinfunction "20_20") (pintype "bidirectional"))
      (node (ref "X-WEST") (pin "67") (pinfunction "67_67") (pintype "bidirectional"))
    )
    (net (code "108") (name "OUT33_P") (class "Default")
      (node (ref "X-NORTH") (pin "22") (pinfunction "22_22") (pintype "bidirectional"))
      (node (ref "X-WEST") (pin "65") (pinfunction "65_65") (pintype "bidirectional"))
    )
    (net (code "109") (name "OUT34_N") (class "Default")
      (node (ref "X-NORTH") (pin "27") (pinfunction "27_27") (pintype "bidirectional"))
    )
    (net (code "110") (name "OUT34_P") (class "Default")
      (node (ref "X-NORTH") (pin "29") (pinfunction "29_29") (pintype "bidirectional"))
    )
    (net (code "111") (name "OUT35_N") (class "Default")
      (node (ref "X-NORTH") (pin "26") (pinfunction "26_26") (pintype "bidirectional"))
      (node (ref "X-WEST") (pin "61") (pinfunction "61_61") (pintype "bidirectional"))
    )
    (net (code "112") (name "OUT35_P") (class "Default")
      (node (ref "X-NORTH") (pin "28") (pinfunction "28_28") (pintype "bidirectional"))
      (node (ref "X-WEST") (pin "59") (pinfunction "59_59") (pintype "bidirectional"))
    )
    (net (code "113") (name "OUT36_N") (class "Default")
      (node (ref "X-NORTH") (pin "33") (pinfunction "33_33") (pintype "bidirectional"))
    )
    (net (code "114") (name "OUT36_P") (class "Default")
      (node (ref "X-NORTH") (pin "35") (pinfunction "35_35") (pintype "bidirectional"))
    )
    (net (code "115") (name "OUT37_N") (class "Default")
      (node (ref "X-NORTH") (pin "32") (pinfunction "32_32") (pintype "bidirectional"))
      (node (ref "X-WEST") (pin "47") (pinfunction "47_47") (pintype "bidirectional"))
    )
    (net (code "116") (name "OUT37_P") (class "Default")
      (node (ref "X-NORTH") (pin "34") (pinfunction "34_34") (pintype "bidirectional"))
      (node (ref "X-WEST") (pin "45") (pinfunction "45_45") (pintype "bidirectional"))
    )
    (net (code "117") (name "OUT38_N") (class "Default")
      (node (ref "X-NORTH") (pin "38") (pinfunction "38_38") (pintype "bidirectional"))
    )
    (net (code "118") (name "OUT38_P") (class "Default")
      (node (ref "X-NORTH") (pin "40") (pinfunction "40_40") (pintype "bidirectional"))
    )
    (net (code "119") (name "OUT39_N") (class "Default")
      (node (ref "X-NORTH") (pin "39") (pinfunction "39_39") (pintype "bidirectional"))
      (node (ref "X-WEST") (pin "80") (pinfunction "80_80") (pintype "bidirectional"))
    )
    (net (code "120") (name "OUT39_P") (class "Default")
      (node (ref "X-NORTH") (pin "41") (pinfunction "41_41") (pintype "bidirectional"))
      (node (ref "X-WEST") (pin "78") (pinfunction "78_78") (pintype "bidirectional"))
    )
    (net (code "121") (name "OUT40_N") (class "Default")
      (node (ref "X-NORTH") (pin "44") (pinfunction "44_44") (pintype "bidirectional"))
    )
    (net (code "122") (name "OUT40_P") (class "Default")
      (node (ref "X-NORTH") (pin "46") (pinfunction "46_46") (pintype "bidirectional"))
    )
    (net (code "123") (name "OUT41_N") (class "Default")
      (node (ref "X-NORTH") (pin "45") (pinfunction "45_45") (pintype "bidirectional"))
      (node (ref "X-WEST") (pin "74") (pinfunction "74_74") (pintype "bidirectional"))
    )
    (net (code "124") (name "OUT41_P") (class "Default")
      (node (ref "X-NORTH") (pin "47") (pinfunction "47_47") (pintype "bidirectional"))
      (node (ref "X-WEST") (pin "72") (pinfunction "72_72") (pintype "bidirectional"))
    )
    (net (code "125") (name "OUT42_N") (class "Default")
      (node (ref "X-NORTH") (pin "50") (pinfunction "50_50") (pintype "bidirectional"))
    )
    (net (code "126") (name "OUT42_P") (class "Default")
      (node (ref "X-NORTH") (pin "52") (pinfunction "52_52") (pintype "bidirectional"))
    )
    (net (code "127") (name "OUT43_N") (class "Default")
      (node (ref "X-NORTH") (pin "51") (pinfunction "51_51") (pintype "bidirectional"))
      (node (ref "X-WEST") (pin "68") (pinfunction "68_68") (pintype "bidirectional"))
    )
    (net (code "128") (name "OUT43_P") (class "Default")
      (node (ref "X-NORTH") (pin "53") (pinfunction "53_53") (pintype "bidirectional"))
      (node (ref "X-WEST") (pin "66") (pinfunction "66_66") (pintype "bidirectional"))
    )
    (net (code "129") (name "OUT44_N") (class "Default")
      (node (ref "X-NORTH") (pin "56") (pinfunction "56_56") (pintype "bidirectional"))
    )
    (net (code "130") (name "OUT44_P") (class "Default")
      (node (ref "X-NORTH") (pin "58") (pinfunction "58_58") (pintype "bidirectional"))
    )
    (net (code "131") (name "OUT45_N") (class "Default")
      (node (ref "X-NORTH") (pin "57") (pinfunction "57_57") (pintype "bidirectional"))
      (node (ref "X-WEST") (pin "62") (pinfunction "62_62") (pintype "bidirectional"))
    )
    (net (code "132") (name "OUT45_P") (class "Default")
      (node (ref "X-NORTH") (pin "59") (pinfunction "59_59") (pintype "bidirectional"))
      (node (ref "X-WEST") (pin "60") (pinfunction "60_60") (pintype "bidirectional"))
    )
    (net (code "133") (name "OUT46_N") (class "Default")
      (node (ref "X-NORTH") (pin "62") (pinfunction "62_62") (pintype "bidirectional"))
    )
    (net (code "134") (name "OUT46_P") (class "Default")
      (node (ref "X-NORTH") (pin "64") (pinfunction "64_64") (pintype "bidirectional"))
    )
    (net (code "135") (name "OUT47_N") (class "Default")
      (node (ref "X-NORTH") (pin "63") (pinfunction "63_63") (pintype "bidirectional"))
      (node (ref "X-WEST") (pin "56") (pinfunction "56_56") (pintype "bidirectional"))
    )
    (net (code "136") (name "OUT47_P") (class "Default")
      (node (ref "X-NORTH") (pin "65") (pinfunction "65_65") (pintype "bidirectional"))
      (node (ref "X-WEST") (pin "54") (pinfunction "54_54") (pintype "bidirectional"))
    )
    (net (code "137") (name "OUT48_N") (class "Default")
      (node (ref "X-NORTH") (pin "68") (pinfunction "68_68") (pintype "bidirectional"))
    )
    (net (code "138") (name "OUT48_P") (class "Default")
      (node (ref "X-NORTH") (pin "70") (pinfunction "70_70") (pintype "bidirectional"))
    )
    (net (code "139") (name "OUT49_N") (class "Default")
      (node (ref "X-EAST") (pin "48") (pinfunction "48_48") (pintype "bidirectional"))
      (node (ref "X-NORTH") (pin "74") (pinfunction "74_74") (pintype "bidirectional"))
    )
    (net (code "140") (name "OUT49_P") (class "Default")
      (node (ref "X-EAST") (pin "46") (pinfunction "46_46") (pintype "bidirectional"))
      (node (ref "X-NORTH") (pin "76") (pinfunction "76_76") (pintype "bidirectional"))
    )
    (net (code "141") (name "OUT50_N") (class "Default")
      (node (ref "X-NORTH") (pin "69") (pinfunction "69_69") (pintype "bidirectional"))
    )
    (net (code "142") (name "OUT50_P") (class "Default")
      (node (ref "X-NORTH") (pin "71") (pinfunction "71_71") (pintype "bidirectional"))
    )
    (net (code "143") (name "OUT51_N") (class "Default")
      (node (ref "X-EAST") (pin "42") (pinfunction "42_42") (pintype "bidirectional"))
      (node (ref "X-NORTH") (pin "80") (pinfunction "80_80") (pintype "bidirectional"))
    )
    (net (code "144") (name "OUT51_P") (class "Default")
      (node (ref "X-EAST") (pin "40") (pinfunction "40_40") (pintype "bidirectional"))
      (node (ref "X-NORTH") (pin "82") (pinfunction "82_82") (pintype "bidirectional"))
    )
    (net (code "145") (name "OUT52_N") (class "Default")
      (node (ref "X-NORTH") (pin "75") (pinfunction "75_75") (pintype "bidirectional"))
    )
    (net (code "146") (name "OUT52_P") (class "Default")
      (node (ref "X-NORTH") (pin "77") (pinfunction "77_77") (pintype "bidirectional"))
    )
    (net (code "147") (name "OUT53_N") (class "Default")
      (node (ref "X-EAST") (pin "47") (pinfunction "47_47") (pintype "bidirectional"))
      (node (ref "X-NORTH") (pin "86") (pinfunction "86_86") (pintype "bidirectional"))
    )
    (net (code "148") (name "OUT53_P") (class "Default")
      (node (ref "X-EAST") (pin "45") (pinfunction "45_45") (pintype "bidirectional"))
      (node (ref "X-NORTH") (pin "88") (pinfunction "88_88") (pintype "bidirectional"))
    )
    (net (code "149") (name "OUT54_N") (class "Default")
      (node (ref "X-NORTH") (pin "81") (pinfunction "81_81") (pintype "bidirectional"))
    )
    (net (code "150") (name "OUT54_P") (class "Default")
      (node (ref "X-NORTH") (pin "83") (pinfunction "83_83") (pintype "bidirectional"))
    )
    (net (code "151") (name "OUT55_N") (class "Default")
      (node (ref "X-EAST") (pin "41") (pinfunction "41_41") (pintype "bidirectional"))
      (node (ref "X-NORTH") (pin "92") (pinfunction "92_92") (pintype "bidirectional"))
    )
    (net (code "152") (name "OUT55_P") (class "Default")
      (node (ref "X-EAST") (pin "39") (pinfunction "39_39") (pintype "bidirectional"))
      (node (ref "X-NORTH") (pin "94") (pinfunction "94_94") (pintype "bidirectional"))
    )
    (net (code "153") (name "OUT56_N") (class "Default")
      (node (ref "X-NORTH") (pin "87") (pinfunction "87_87") (pintype "bidirectional"))
    )
    (net (code "154") (name "OUT56_P") (class "Default")
      (node (ref "X-NORTH") (pin "89") (pinfunction "89_89") (pintype "bidirectional"))
    )
    (net (code "155") (name "OUT57_N") (class "Default")
      (node (ref "X-EAST") (pin "35") (pinfunction "35_35") (pintype "bidirectional"))
      (node (ref "X-NORTH") (pin "98") (pinfunction "98_98") (pintype "bidirectional"))
    )
    (net (code "156") (name "OUT57_P") (class "Default")
      (node (ref "X-EAST") (pin "33") (pinfunction "33_33") (pintype "bidirectional"))
      (node (ref "X-NORTH") (pin "100") (pinfunction "100_100") (pintype "bidirectional"))
    )
    (net (code "157") (name "OUT58_N") (class "Default")
      (node (ref "X-NORTH") (pin "93") (pinfunction "93_93") (pintype "bidirectional"))
    )
    (net (code "158") (name "OUT58_P") (class "Default")
      (node (ref "X-NORTH") (pin "95") (pinfunction "95_95") (pintype "bidirectional"))
    )
    (net (code "159") (name "OUT59_N") (class "Default")
      (node (ref "X-EAST") (pin "27") (pinfunction "27_27") (pintype "bidirectional"))
      (node (ref "X-NORTH") (pin "104") (pinfunction "104_104") (pintype "bidirectional"))
    )
    (net (code "160") (name "OUT59_P") (class "Default")
      (node (ref "X-EAST") (pin "25") (pinfunction "25_25") (pintype "bidirectional"))
      (node (ref "X-NORTH") (pin "106") (pinfunction "106_106") (pintype "bidirectional"))
    )
    (net (code "161") (name "OUT60_N") (class "Default")
      (node (ref "X-NORTH") (pin "110") (pinfunction "110_110") (pintype "bidirectional"))
    )
    (net (code "162") (name "OUT60_P") (class "Default")
      (node (ref "X-NORTH") (pin "112") (pinfunction "112_112") (pintype "bidirectional"))
    )
    (net (code "163") (name "OUT61_N") (class "Default")
      (node (ref "X-EAST") (pin "36") (pinfunction "36_36") (pintype "bidirectional"))
      (node (ref "X-NORTH") (pin "99") (pinfunction "99_99") (pintype "bidirectional"))
    )
    (net (code "164") (name "OUT61_P") (class "Default")
      (node (ref "X-EAST") (pin "34") (pinfunction "34_34") (pintype "bidirectional"))
      (node (ref "X-NORTH") (pin "101") (pinfunction "101_101") (pintype "bidirectional"))
    )
    (net (code "165") (name "OUT62_N") (class "Default")
      (node (ref "X-NORTH") (pin "116") (pinfunction "116_116") (pintype "bidirectional"))
    )
    (net (code "166") (name "OUT62_P") (class "Default")
      (node (ref "X-NORTH") (pin "118") (pinfunction "118_118") (pintype "bidirectional"))
    )
    (net (code "167") (name "OUT63_N") (class "Default")
      (node (ref "X-EAST") (pin "30") (pinfunction "30_30") (pintype "bidirectional"))
      (node (ref "X-NORTH") (pin "105") (pinfunction "105_105") (pintype "bidirectional"))
    )
    (net (code "168") (name "OUT63_P") (class "Default")
      (node (ref "X-EAST") (pin "28") (pinfunction "28_28") (pintype "bidirectional"))
      (node (ref "X-NORTH") (pin "107") (pinfunction "107_107") (pintype "bidirectional"))
    )
    (net (code "169") (name "OUT64_N") (class "Default")
      (node (ref "X-NORTH") (pin "111") (pinfunction "111_111") (pintype "bidirectional"))
    )
    (net (code "170") (name "OUT64_P") (class "Default")
      (node (ref "X-NORTH") (pin "113") (pinfunction "113_113") (pintype "bidirectional"))
    )
    (net (code "171") (name "OUTCLK_N") (class "Default")
      (node (ref "X-NORTH") (pin "15") (pinfunction "15_15") (pintype "bidirectional"))
      (node (ref "X-WEST") (pin "53") (pinfunction "53_53") (pintype "bidirectional"))
    )
    (net (code "172") (name "OUTCLK_P") (class "Default")
      (node (ref "X-NORTH") (pin "17") (pinfunction "17_17") (pintype "bidirectional"))
      (node (ref "X-WEST") (pin "55") (pinfunction "55_55") (pintype "bidirectional"))
    )
    (net (code "173") (name "OUTCTR_N") (class "Default")
      (node (ref "X-SOUTH") (pin "125") (pinfunction "125_125") (pintype "bidirectional"))
      (node (ref "X-WEST") (pin "22") (pinfunction "22_22") (pintype "bidirectional"))
    )
    (net (code "174") (name "OUTCTR_P") (class "Default")
      (node (ref "X-SOUTH") (pin "123") (pinfunction "123_123") (pintype "bidirectional"))
      (node (ref "X-WEST") (pin "24") (pinfunction "24_24") (pintype "bidirectional"))
    )
    (net (code "175") (name "S00_N") (class "Default")
      (node (ref "X-SOUTH") (pin "16") (pinfunction "16_16") (pintype "bidirectional"))
    )
    (net (code "176") (name "S00_P") (class "Default")
      (node (ref "X-SOUTH") (pin "14") (pinfunction "14_14") (pintype "bidirectional"))
    )
    (net (code "177") (name "S01_N") (class "Default")
      (node (ref "X-SOUTH") (pin "17") (pinfunction "17_17") (pintype "bidirectional"))
    )
    (net (code "178") (name "S01_P") (class "Default")
      (node (ref "X-SOUTH") (pin "15") (pinfunction "15_15") (pintype "bidirectional"))
    )
    (net (code "179") (name "S02_N") (class "Default")
      (node (ref "X-SOUTH") (pin "22") (pinfunction "22_22") (pintype "bidirectional"))
    )
    (net (code "180") (name "S02_P") (class "Default")
      (node (ref "X-SOUTH") (pin "20") (pinfunction "20_20") (pintype "bidirectional"))
    )
    (net (code "181") (name "S03_N") (class "Default")
      (node (ref "X-SOUTH") (pin "23") (pinfunction "23_23") (pintype "bidirectional"))
    )
    (net (code "182") (name "S03_P") (class "Default")
      (node (ref "X-SOUTH") (pin "21") (pinfunction "21_21") (pintype "bidirectional"))
    )
    (net (code "183") (name "S05_N") (class "Default")
      (node (ref "X-SOUTH") (pin "29") (pinfunction "29_29") (pintype "bidirectional"))
    )
    (net (code "184") (name "S05_P") (class "Default")
      (node (ref "X-SOUTH") (pin "27") (pinfunction "27_27") (pintype "bidirectional"))
    )
    (net (code "185") (name "S38_N") (class "Default")
      (node (ref "X-SOUTH") (pin "130") (pinfunction "130_130") (pintype "bidirectional"))
    )
    (net (code "186") (name "S38_P") (class "Default")
      (node (ref "X-SOUTH") (pin "128") (pinfunction "128_128") (pintype "bidirectional"))
    )
    (net (code "187") (name "S39_N") (class "Default")
      (node (ref "X-SOUTH") (pin "131") (pinfunction "131_131") (pintype "bidirectional"))
    )
    (net (code "188") (name "S39_P") (class "Default")
      (node (ref "X-SOUTH") (pin "129") (pinfunction "129_129") (pintype "bidirectional"))
    )
    (net (code "189") (name "SPI_EN") (class "Default")
      (node (ref "X-EAST") (pin "14") (pinfunction "14_14") (pintype "bidirectional"))
      (node (ref "X-NORTH") (pin "119") (pinfunction "119_119") (pintype "bidirectional"))
    )
    (net (code "190") (name "SYS_RES_N") (class "Default")
      (node (ref "X-EAST") (pin "22") (pinfunction "22_22") (pintype "bidirectional"))
      (node (ref "X-NORTH") (pin "125") (pinfunction "125_125") (pintype "bidirectional"))
    )
    (net (code "191") (name "S_CHK_V") (class "Default")
      (node (ref "X-EAST") (pin "92") (pinfunction "92_92") (pintype "bidirectional"))
      (node (ref "X-EAST") (pin "94") (pinfunction "94_94") (pintype "bidirectional"))
      (node (ref "X-SOUTH") (pin "10") (pinfunction "10_10") (pintype "bidirectional"))
      (node (ref "X-SOUTH") (pin "8") (pinfunction "8_8") (pintype "bidirectional"))
    )
    (net (code "192") (name "S_I2C_V") (class "Default")
      (node (ref "X-SOUTH") (pin "135") (pinfunction "135_135") (pintype "bidirectional"))
      (node (ref "X-SOUTH") (pin "137") (pinfunction "137_137") (pintype "bidirectional"))
      (node (ref "X-WEST") (pin "7") (pinfunction "7_7") (pintype "bidirectional"))
      (node (ref "X-WEST") (pin "9") (pinfunction "9_9") (pintype "bidirectional"))
    )
    (net (code "193") (name "S_SCK") (class "Default")
      (node (ref "X-SOUTH") (pin "144") (pinfunction "144_144") (pintype "bidirectional"))
      (node (ref "X-WEST") (pin "2") (pinfunction "2_2") (pintype "bidirectional"))
    )
    (net (code "194") (name "S_SCL") (class "Default")
      (node (ref "X-SOUTH") (pin "143") (pinfunction "143_143") (pintype "bidirectional"))
      (node (ref "X-WEST") (pin "1") (pinfunction "1_1") (pintype "bidirectional"))
    )
    (net (code "195") (name "S_SDA") (class "Default")
      (node (ref "X-SOUTH") (pin "141") (pinfunction "141_141") (pintype "bidirectional"))
      (node (ref "X-WEST") (pin "3") (pinfunction "3_3") (pintype "bidirectional"))
    )
    (net (code "196") (name "S_SDI") (class "Default")
      (node (ref "X-SOUTH") (pin "140") (pinfunction "140_140") (pintype "bidirectional"))
      (node (ref "X-WEST") (pin "6") (pinfunction "6_6") (pintype "bidirectional"))
    )
    (net (code "197") (name "S_SDO") (class "Default")
      (node (ref "X-SOUTH") (pin "142") (pinfunction "142_142") (pintype "bidirectional"))
      (node (ref "X-WEST") (pin "4") (pinfunction "4_4") (pintype "bidirectional"))
    )
    (net (code "198") (name "S_SPI_V") (class "Default")
      (node (ref "X-SOUTH") (pin "134") (pinfunction "134_134") (pintype "bidirectional"))
      (node (ref "X-SOUTH") (pin "136") (pinfunction "136_136") (pintype "bidirectional"))
      (node (ref "X-WEST") (pin "10") (pinfunction "10_10") (pintype "bidirectional"))
      (node (ref "X-WEST") (pin "8") (pinfunction "8_8") (pintype "bidirectional"))
    )
    (net (code "199") (name "S_VE") (class "Default")
      (node (ref "C7") (pin "1") (pinfunction "1_1") (pintype "passive"))
      (node (ref "SE") (pin "1") (pinfunction "1_1") (pintype "passive"))
      (node (ref "X-SOUTH") (pin "13") (pinfunction "13_13") (pintype "bidirectional"))
      (node (ref "X-SOUTH") (pin "19") (pinfunction "19_19") (pintype "bidirectional"))
      (node (ref "X-SOUTH") (pin "31") (pinfunction "31_31") (pintype "bidirectional"))
      (node (ref "X-SOUTH") (pin "37") (pinfunction "37_37") (pintype "bidirectional"))
    )
    (net (code "200") (name "S_VE_CV") (class "Default")
      (node (ref "X-EAST") (pin "100") (pinfunction "100_100") (pintype "bidirectional"))
      (node (ref "X-SOUTH") (pin "2") (pinfunction "2_2") (pintype "bidirectional"))
    )
    (net (code "201") (name "S_VE_OV") (class "Default")
      (node (ref "X-EAST") (pin "99") (pinfunction "99_99") (pintype "bidirectional"))
      (node (ref "X-SOUTH") (pin "1") (pinfunction "1_1") (pintype "bidirectional"))
    )
    (net (code "202") (name "S_VE_RS") (class "Default")
      (node (ref "X-EAST") (pin "84") (pinfunction "84_84") (pintype "bidirectional"))
      (node (ref "X-SOUTH") (pin "25") (pinfunction "25_25") (pintype "bidirectional"))
    )
    (net (code "203") (name "S_VE_UV") (class "Default")
      (node (ref "X-EAST") (pin "89") (pinfunction "89_89") (pintype "bidirectional"))
      (node (ref "X-SOUTH") (pin "7") (pinfunction "7_7") (pintype "bidirectional"))
    )
    (net (code "204") (name "S_VS") (class "Default")
      (node (ref "C6") (pin "1") (pinfunction "1_1") (pintype "passive"))
      (node (ref "SW") (pin "1") (pinfunction "1_1") (pintype "passive"))
      (node (ref "X-SOUTH") (pin "49") (pinfunction "49_49") (pintype "bidirectional"))
      (node (ref "X-SOUTH") (pin "55") (pinfunction "55_55") (pintype "bidirectional"))
      (node (ref "X-SOUTH") (pin "61") (pinfunction "61_61") (pintype "bidirectional"))
      (node (ref "X-SOUTH") (pin "67") (pinfunction "67_67") (pintype "bidirectional"))
      (node (ref "X-SOUTH") (pin "79") (pinfunction "79_79") (pintype "bidirectional"))
      (node (ref "X-SOUTH") (pin "85") (pinfunction "85_85") (pintype "bidirectional"))
      (node (ref "X-SOUTH") (pin "91") (pinfunction "91_91") (pintype "bidirectional"))
      (node (ref "X-SOUTH") (pin "97") (pinfunction "97_97") (pintype "bidirectional"))
    )
    (net (code "205") (name "S_VS_CV") (class "Default")
      (node (ref "X-EAST") (pin "98") (pinfunction "98_98") (pintype "bidirectional"))
      (node (ref "X-SOUTH") (pin "4") (pinfunction "4_4") (pintype "bidirectional"))
    )
    (net (code "206") (name "S_VS_OV") (class "Default")
      (node (ref "X-EAST") (pin "97") (pinfunction "97_97") (pintype "bidirectional"))
      (node (ref "X-SOUTH") (pin "3") (pinfunction "3_3") (pintype "bidirectional"))
    )
    (net (code "207") (name "S_VS_RS") (class "Default")
      (node (ref "X-EAST") (pin "86") (pinfunction "86_86") (pintype "bidirectional"))
      (node (ref "X-SOUTH") (pin "73") (pinfunction "73_73") (pintype "bidirectional"))
    )
    (net (code "208") (name "S_VS_UV") (class "Default")
      (node (ref "X-EAST") (pin "87") (pinfunction "87_87") (pintype "bidirectional"))
      (node (ref "X-SOUTH") (pin "9") (pinfunction "9_9") (pintype "bidirectional"))
    )
    (net (code "209") (name "S_VW") (class "Default")
      (node (ref "C2") (pin "1") (pinfunction "1_1") (pintype "passive"))
      (node (ref "SW") (pin "2") (pinfunction "2_2") (pintype "passive"))
      (node (ref "X-SOUTH") (pin "109") (pinfunction "109_109") (pintype "bidirectional"))
      (node (ref "X-SOUTH") (pin "115") (pinfunction "115_115") (pintype "bidirectional"))
      (node (ref "X-SOUTH") (pin "127") (pinfunction "127_127") (pintype "bidirectional"))
      (node (ref "X-SOUTH") (pin "133") (pinfunction "133_133") (pintype "bidirectional"))
    )
    (net (code "210") (name "S_VW_CV") (class "Default")
      (node (ref "X-EAST") (pin "96") (pinfunction "96_96") (pintype "bidirectional"))
      (node (ref "X-SOUTH") (pin "6") (pinfunction "6_6") (pintype "bidirectional"))
    )
    (net (code "211") (name "S_VW_OV") (class "Default")
      (node (ref "X-EAST") (pin "95") (pinfunction "95_95") (pintype "bidirectional"))
      (node (ref "X-SOUTH") (pin "5") (pinfunction "5_5") (pintype "bidirectional"))
    )
    (net (code "212") (name "S_VW_RS") (class "Default")
      (node (ref "X-EAST") (pin "88") (pinfunction "88_88") (pintype "bidirectional"))
      (node (ref "X-SOUTH") (pin "121") (pinfunction "121_121") (pintype "bidirectional"))
    )
    (net (code "213") (name "S_VW_UV") (class "Default")
      (node (ref "X-EAST") (pin "85") (pinfunction "85_85") (pintype "bidirectional"))
      (node (ref "X-SOUTH") (pin "11") (pinfunction "11_11") (pintype "bidirectional"))
    )
    (net (code "214") (name "TCK") (class "Default")
      (node (ref "X-WEST") (pin "12") (pinfunction "12_12") (pintype "bidirectional"))
    )
    (net (code "215") (name "TDI") (class "Default")
      (node (ref "X-WEST") (pin "16") (pinfunction "16_16") (pintype "bidirectional"))
    )
    (net (code "216") (name "TDIG1") (class "Default")
      (node (ref "X-EAST") (pin "18") (pinfunction "18_18") (pintype "bidirectional"))
      (node (ref "X-NORTH") (pin "123") (pinfunction "123_123") (pintype "bidirectional"))
    )
    (net (code "217") (name "TDIG2") (class "Default")
      (node (ref "X-EAST") (pin "17") (pinfunction "17_17") (pintype "bidirectional"))
      (node (ref "X-NORTH") (pin "130") (pinfunction "130_130") (pintype "bidirectional"))
    )
    (net (code "218") (name "TDO") (class "Default")
      (node (ref "X-WEST") (pin "18") (pinfunction "18_18") (pintype "bidirectional"))
    )
    (net (code "219") (name "TMS") (class "Default")
      (node (ref "X-WEST") (pin "14") (pinfunction "14_14") (pintype "bidirectional"))
    )
    (net (code "220") (name "T_EXP1") (class "Default")
      (node (ref "X-EAST") (pin "12") (pinfunction "12_12") (pintype "bidirectional"))
      (node (ref "X-NORTH") (pin "131") (pinfunction "131_131") (pintype "bidirectional"))
    )
    (net (code "221") (name "T_EXP2") (class "Default")
      (node (ref "X-EAST") (pin "16") (pinfunction "16_16") (pintype "bidirectional"))
      (node (ref "X-NORTH") (pin "117") (pinfunction "117_117") (pintype "bidirectional"))
    )
    (net (code "222") (name "W_I2C_V") (class "Default")
      (node (ref "X-WEST") (pin "11") (pinfunction "11_11") (pintype "bidirectional"))
      (node (ref "X-WEST") (pin "13") (pinfunction "13_13") (pintype "bidirectional"))
    )
    (net (code "223") (name "W_SCL") (class "Default")
      (node (ref "X-WEST") (pin "15") (pinfunction "15_15") (pintype "bidirectional"))
    )
    (net (code "224") (name "W_SDA") (class "Default")
      (node (ref "X-WEST") (pin "17") (pinfunction "17_17") (pintype "bidirectional"))
    )
    (net (code "225") (name "W_VW") (class "Default")
      (node (ref "C8") (pin "1") (pinfunction "1_1") (pintype "passive"))
      (node (ref "NW") (pin "2") (pinfunction "2_2") (pintype "passive"))
    )
    (net (code "226") (name "W_VW_CV") (class "Default")
      (node (ref "X-WEST") (pin "90") (pinfunction "90_90") (pintype "bidirectional"))
    )
    (net (code "227") (name "W_VW_OV") (class "Default")
      (node (ref "X-WEST") (pin "93") (pinfunction "93_93") (pintype "bidirectional"))
    )
    (net (code "228") (name "W_VW_UV") (class "Default")
      (node (ref "X-WEST") (pin "91") (pinfunction "91_91") (pintype "bidirectional"))
    )
    (net (code "229") (name "unconnected-(X-EAST-Pad79)") (class "Default")
      (node (ref "X-EAST") (pin "79") (pinfunction "79_79") (pintype "bidirectional"))
    )
    (net (code "230") (name "unconnected-(X-EAST-Pad81)") (class "Default")
      (node (ref "X-EAST") (pin "81") (pinfunction "81_81") (pintype "bidirectional"))
    )
    (net (code "231") (name "unconnected-(X-EAST-Pad83)") (class "Default")
      (node (ref "X-EAST") (pin "83") (pinfunction "83_83") (pintype "bidirectional"))
    )
    (net (code "232") (name "unconnected-(X-EAST-PadM1)") (class "Default")
      (node (ref "X-EAST") (pin "M1") (pinfunction "M1_M1") (pintype "bidirectional"))
    )
    (net (code "233") (name "unconnected-(X-EAST-PadM2)") (class "Default")
      (node (ref "X-EAST") (pin "M2") (pinfunction "M2_M2") (pintype "bidirectional"))
    )
    (net (code "234") (name "unconnected-(X-NORTH-PadM1)") (class "Default")
      (node (ref "X-NORTH") (pin "M1") (pinfunction "M1_M1") (pintype "bidirectional"))
    )
    (net (code "235") (name "unconnected-(X-NORTH-PadM2)") (class "Default")
      (node (ref "X-NORTH") (pin "M2") (pinfunction "M2_M2") (pintype "bidirectional"))
    )
    (net (code "236") (name "unconnected-(X-SOUTH-PadM1)") (class "Default")
      (node (ref "X-SOUTH") (pin "M1") (pinfunction "M1_M1") (pintype "bidirectional"))
    )
    (net (code "237") (name "unconnected-(X-SOUTH-PadM2)") (class "Default")
      (node (ref "X-SOUTH") (pin "M2") (pinfunction "M2_M2") (pintype "bidirectional"))
    )
    (net (code "238") (name "unconnected-(X-WEST-Pad79)") (class "Default")
      (node (ref "X-WEST") (pin "79") (pinfunction "79_79") (pintype "bidirectional"))
    )
    (net (code "239") (name "unconnected-(X-WEST-Pad81)") (class "Default")
      (node (ref "X-WEST") (pin "81") (pinfunction "81_81") (pintype "bidirectional"))
    )
    (net (code "240") (name "unconnected-(X-WEST-Pad83)") (class "Default")
      (node (ref "X-WEST") (pin "83") (pinfunction "83_83") (pintype "bidirectional"))
    )
    (net (code "241") (name "unconnected-(X-WEST-PadM1)") (class "Default")
      (node (ref "X-WEST") (pin "M1") (pinfunction "M1_M1") (pintype "bidirectional"))
    )
    (net (code "242") (name "unconnected-(X-WEST-PadM2)") (class "Default")
      (node (ref "X-WEST") (pin "M2") (pinfunction "M2_M2") (pintype "bidirectional"))
    )
  )
)
